# esquematico-educaino-V2.net
KiCad netlist of a schematic drawn in EAGLE
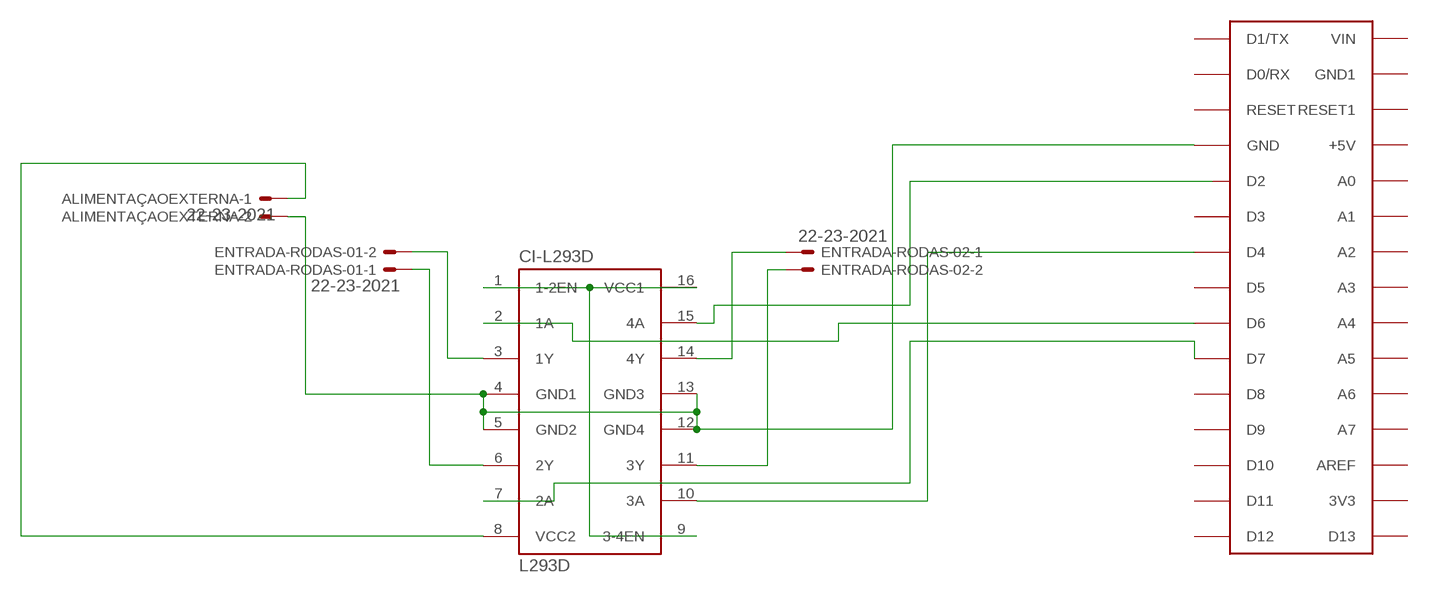
[diagram p0: schematic, sheet 1]

(export (version "E")
  (design (tool "Eeschema 10.0.6"))
  (components
    (comp (ref "ALIMENTAÇAOEXTERNA")
      (value "22-23-2021")
      (footprint "eagle-import:22-23-2021")
      (fields (field (name "MF") "MOLEX"))
      (libsource (lib "eagle-import") (part "22-23-2021"))
    )
    (comp (ref "CI-L293D")
      (value "L293D")
      (footprint "eagle-import:DIL16")
      (libsource (lib "eagle-import") (part "L293D"))
    )
    (comp (ref "ENTRADA-RODAS-01")
      (value "22-23-2021")
      (footprint "eagle-import:22-23-2021")
      (fields (field (name "MF") "MOLEX"))
      (libsource (lib "eagle-import") (part "22-23-2021"))
    )
    (comp (ref "ENTRADA-RODAS-02")
      (value "22-23-2021")
      (footprint "eagle-import:22-23-2021")
      (fields (field (name "MF") "MOLEX"))
      (libsource (lib "eagle-import") (part "22-23-2021"))
    )
    (comp (ref "U$1")
      (value "ARDUINONANO")
      (footprint "eagle-import:PDIP-32")
      (libsource (lib "eagle-import") (part "ARDUINONANO"))
    )
  )
  (nets
    (net (code "1") (name "Net-(ALIMENTAÇAOEXTERNAA-S)") (class "Default")
      (node (ref "ALIMENTAÇAOEXTERNA") (pin "1") (pinfunction "S_1") (pintype "passive"))
      (node (ref "CI-L293D") (pin "8") (pinfunction "VCC2_8") (pintype "power_in"))
    )
    (net (code "2") (name "Net-(ALIMENTAÇAOEXTERNAB-S)") (class "Default")
      (node (ref "ALIMENTAÇAOEXTERNA") (pin "2") (pinfunction "S_2") (pintype "passive"))
      (node (ref "CI-L293D") (pin "12") (pinfunction "GND4_12") (pintype "power_in"))
      (node (ref "CI-L293D") (pin "13") (pinfunction "GND3_13") (pintype "power_in"))
      (node (ref "CI-L293D") (pin "4") (pinfunction "GND1_4") (pintype "power_in"))
      (node (ref "CI-L293D") (pin "5") (pinfunction "GND2_5") (pintype "power_in"))
      (node (ref "U$1") (pin "GND") (pinfunction "GND_GND") (pintype "bidirectional"))
    )
    (net (code "3") (name "Net-(CI-L293D-1-2EN)") (class "Default")
      (node (ref "CI-L293D") (pin "1") (pinfunction "1-2EN_1") (pintype "input"))
      (node (ref "CI-L293D") (pin "16") (pinfunction "VCC1_16") (pintype "power_in"))
      (node (ref "CI-L293D") (pin "9") (pinfunction "3-4EN_9") (pintype "input"))
    )
    (net (code "4") (name "Net-(CI-L293D-1A)") (class "Default")
      (node (ref "CI-L293D") (pin "2") (pinfunction "1A_2") (pintype "input"))
      (node (ref "U$1") (pin "D6") (pinfunction "D6_D6") (pintype "bidirectional"))
    )
    (net (code "5") (name "Net-(CI-L293D-1Y)") (class "Default")
      (node (ref "CI-L293D") (pin "3") (pinfunction "1Y_3") (pintype "output"))
      (node (ref "ENTRADA-RODAS-01") (pin "2") (pinfunction "S_2") (pintype "passive"))
    )
    (net (code "6") (name "Net-(CI-L293D-2A)") (class "Default")
      (node (ref "CI-L293D") (pin "7") (pinfunction "2A_7") (pintype "input"))
      (node (ref "U$1") (pin "D7") (pinfunction "D7_D7") (pintype "bidirectional"))
    )
    (net (code "7") (name "Net-(CI-L293D-2Y)") (class "Default")
      (node (ref "CI-L293D") (pin "6") (pinfunction "2Y_6") (pintype "output"))
      (node (ref "ENTRADA-RODAS-01") (pin "1") (pinfunction "S_1") (pintype "passive"))
    )
    (net (code "8") (name "Net-(CI-L293D-3A)") (class "Default")
      (node (ref "CI-L293D") (pin "10") (pinfunction "3A_10") (pintype "input"))
      (node (ref "U$1") (pin "D4") (pinfunction "D4_D4") (pintype "bidirectional"))
    )
    (net (code "9") (name "Net-(CI-L293D-3Y)") (class "Default")
      (node (ref "CI-L293D") (pin "11") (pinfunction "3Y_11") (pintype "output"))
      (node (ref "ENTRADA-RODAS-02") (pin "2") (pinfunction "S_2") (pintype "passive"))
    )
    (net (code "10") (name "Net-(CI-L293D-4Y)") (class "Default")
      (node (ref "CI-L293D") (pin "14") (pinfunction "4Y_14") (pintype "output"))
      (node (ref "ENTRADA-RODAS-02") (pin "1") (pinfunction "S_1") (pintype "passive"))
    )
    (net (code "11") (name "unconnected-(CI-L293D-4A-Pad15)") (class "Default")
      (node (ref "CI-L293D") (pin "15") (pinfunction "4A_15") (pintype "input"))
    )
    (net (code "12") (name "unconnected-(U$1-Pad+5V)") (class "Default")
      (node (ref "U$1") (pin "+5V") (pinfunction "+5V_+5V") (pintype "bidirectional"))
    )
    (net (code "13") (name "unconnected-(U$1-Pad3V3)") (class "Default")
      (node (ref "U$1") (pin "3V3") (pinfunction "3V3_3V3") (pintype "bidirectional"))
    )
    (net (code "14") (name "unconnected-(U$1-PadA0)") (class "Default")
      (node (ref "U$1") (pin "A0") (pinfunction "A0_A0") (pintype "bidirectional"))
    )
    (net (code "15") (name "unconnected-(U$1-PadA1)") (class "Default")
      (node (ref "U$1") (pin "A1") (pinfunction "A1_A1") (pintype "bidirectional"))
    )
    (net (code "16") (name "unconnected-(U$1-PadA2)") (class "Default")
      (node (ref "U$1") (pin "A2") (pinfunction "A2_A2") (pintype "bidirectional"))
    )
    (net (code "17") (name "unconnected-(U$1-PadA3)") (class "Default")
      (node (ref "U$1") (pin "A3") (pinfunction "A3_A3") (pintype "bidirectional"))
    )
    (net (code "18") (name "unconnected-(U$1-PadA4)") (class "Default")
      (node (ref "U$1") (pin "A4") (pinfunction "A4_A4") (pintype "bidirectional"))
    )
    (net (code "19") (name "unconnected-(U$1-PadA5)") (class "Default")
      (node (ref "U$1") (pin "A5") (pinfunction "A5_A5") (pintype "bidirectional"))
    )
    (net (code "20") (name "unconnected-(U$1-PadA6)") (class "Default")
      (node (ref "U$1") (pin "A6") (pinfunction "A6_A6") (pintype "bidirectional"))
    )
    (net (code "21") (name "unconnected-(U$1-PadA7)") (class "Default")
      (node (ref "U$1") (pin "A7") (pinfunction "A7_A7") (pintype "bidirectional"))
    )
    (net (code "22") (name "unconnected-(U$1-PadAREF)") (class "Default")
      (node (ref "U$1") (pin "AREF") (pinfunction "AREF_AREF") (pintype "bidirectional"))
    )
    (net (code "23") (name "unconnected-(U$1-PadD0{slash}RX)") (class "Default")
      (node (ref "U$1") (pin "D0/RX") (pinfunction "D0/RX_D0/RX") (pintype "bidirectional"))
    )
    (net (code "24") (name "unconnected-(U$1-PadD1{slash}TX)") (class "Default")
      (node (ref "U$1") (pin "D1/TX") (pinfunction "D1/TX_D1/TX") (pintype "bidirectional"))
    )
    (net (code "25") (name "unconnected-(U$1-PadD2)") (class "Default")
      (node (ref "U$1") (pin "D2") (pinfunction "D2_D2") (pintype "bidirectional"))
    )
    (net (code "26") (name "unconnected-(U$1-PadD3)") (class "Default")
      (node (ref "U$1") (pin "D3") (pinfunction "D3_D3") (pintype "bidirectional"))
    )
    (net (code "27") (name "unconnected-(U$1-PadD5)") (class "Default")
      (node (ref "U$1") (pin "D5") (pinfunction "D5_D5") (pintype "bidirectional"))
    )
    (net (code "28") (name "unconnected-(U$1-PadD8)") (class "Default")
      (node (ref "U$1") (pin "D8") (pinfunction "D8_D8") (pintype "bidirectional"))
    )
    (net (code "29") (name "unconnected-(U$1-PadD9)") (class "Default")
      (node (ref "U$1") (pin "D9") (pinfunction "D9_D9") (pintype "bidirectional"))
    )
    (net (code "30") (name "unconnected-(U$1-PadD10)") (class "Default")
      (node (ref "U$1") (pin "D10") (pinfunction "D10_D10") (pintype "bidirectional"))
    )
    (net (code "31") (name "unconnected-(U$1-PadD11)") (class "Default")
      (node (ref "U$1") (pin "D11") (pinfunction "D11_D11") (pintype "bidirectional"))
    )
    (net (code "32") (name "unconnected-(U$1-PadD12)") (class "Default")
      (node (ref "U$1") (pin "D12") (pinfunction "D12_D12") (pintype "bidirectional"))
    )
    (net (code "33") (name "unconnected-(U$1-PadD13)") (class "Default")
      (node (ref "U$1") (pin "D13") (pinfunction "D13_D13") (pintype "bidirectional"))
    )
    (net (code "34") (name "unconnected-(U$1-PadGND1)") (class "Default")
      (node (ref "U$1") (pin "GND1") (pinfunction "GND1_GND1") (pintype "bidirectional"))
    )
    (net (code "35") (name "unconnected-(U$1-PadRESET)") (class "Default")
      (node (ref "U$1") (pin "RESET") (pinfunction "RESET_RESET") (pintype "bidirectional"))
    )
    (net (code "36") (name "unconnected-(U$1-PadRESET1)") (class "Default")
      (node (ref "U$1") (pin "RESET1") (pinfunction "RESET1_RESET1") (pintype "bidirectional"))
    )
    (net (code "37") (name "unconnected-(U$1-PadVIN)") (class "Default")
      (node (ref "U$1") (pin "VIN") (pinfunction "VIN_VIN") (pintype "bidirectional"))
    )
  )
)
